# V1_0.net
KiCad netlist of a schematic drawn in Altium Designer
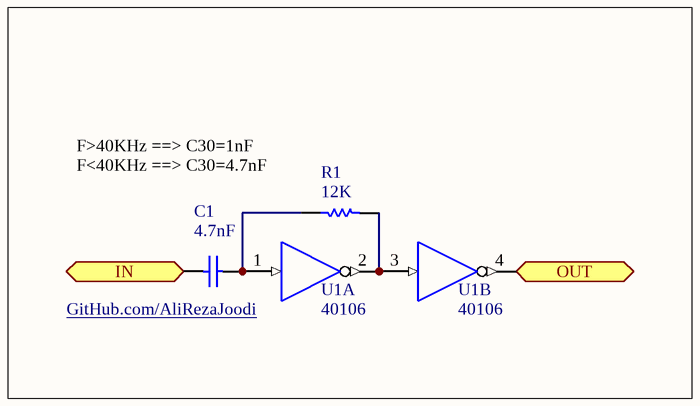
[diagram p0: V1.0.SchDoc]

(export (version "E")
  (design (tool "Eeschema 10.0.6"))
  (components
    (comp (ref "C1")
      (value "4.7nF")
      (footprint "RESC3216N")
      (description "Capacitor")
      (fields (field (name "Comment") "Cap") (field (name "PUBLISHER") "Altium Limited"))
      (libsource (lib "Miscellaneous Devices") (part "Cap"))
    )
    (comp (ref "R1")
      (value "12K")
      (footprint "0805")
      (description "Resistor")
      (fields (field (name "Comment") "Res1") (field (name "PUBLISHER") "Altium Limited"))
      (libsource (lib "Miscellaneous Devices") (part "Res1"))
    )
    (comp (ref "U1")
      (value "40106")
      (footprint "SOP127P636-14N")
      (description "Hex inverting Schmitt trigger, 14-Pin")
      (fields (field (name "PUBLISHER") "Altium Limited"))
      (libsource (lib "my Libraries") (part "40106"))
    )
  )
  (nets
    (net (code "1") (name "/IN") (class "Default")
      (node (ref "C1") (pin "2") (pinfunction "2_2") (pintype "passive"))
    )
    (net (code "2") (name "/OUT") (class "Default")
      (node (ref "U1") (pin "4") (pinfunction "~{O}_4") (pintype "output"))
    )
    (net (code "3") (name "Net-(U1A-I)") (class "Default")
      (node (ref "C1") (pin "1") (pinfunction "1_1") (pintype "passive"))
      (node (ref "R1") (pin "1") (pinfunction "1_1") (pintype "passive"))
      (node (ref "U1") (pin "1") (pinfunction "I_1") (pintype "input"))
    )
    (net (code "4") (name "Net-(U1A-~{O})") (class "Default")
      (node (ref "R1") (pin "2") (pinfunction "2_2") (pintype "passive"))
      (node (ref "U1") (pin "2") (pinfunction "~{O}_2") (pintype "output"))
      (node (ref "U1") (pin "3") (pinfunction "I_3") (pintype "input"))
    )
  )
)
